# P03_Processor_2_or_3_USB_and_Serial.net
KiCad netlist of a schematic drawn in Altium Designer
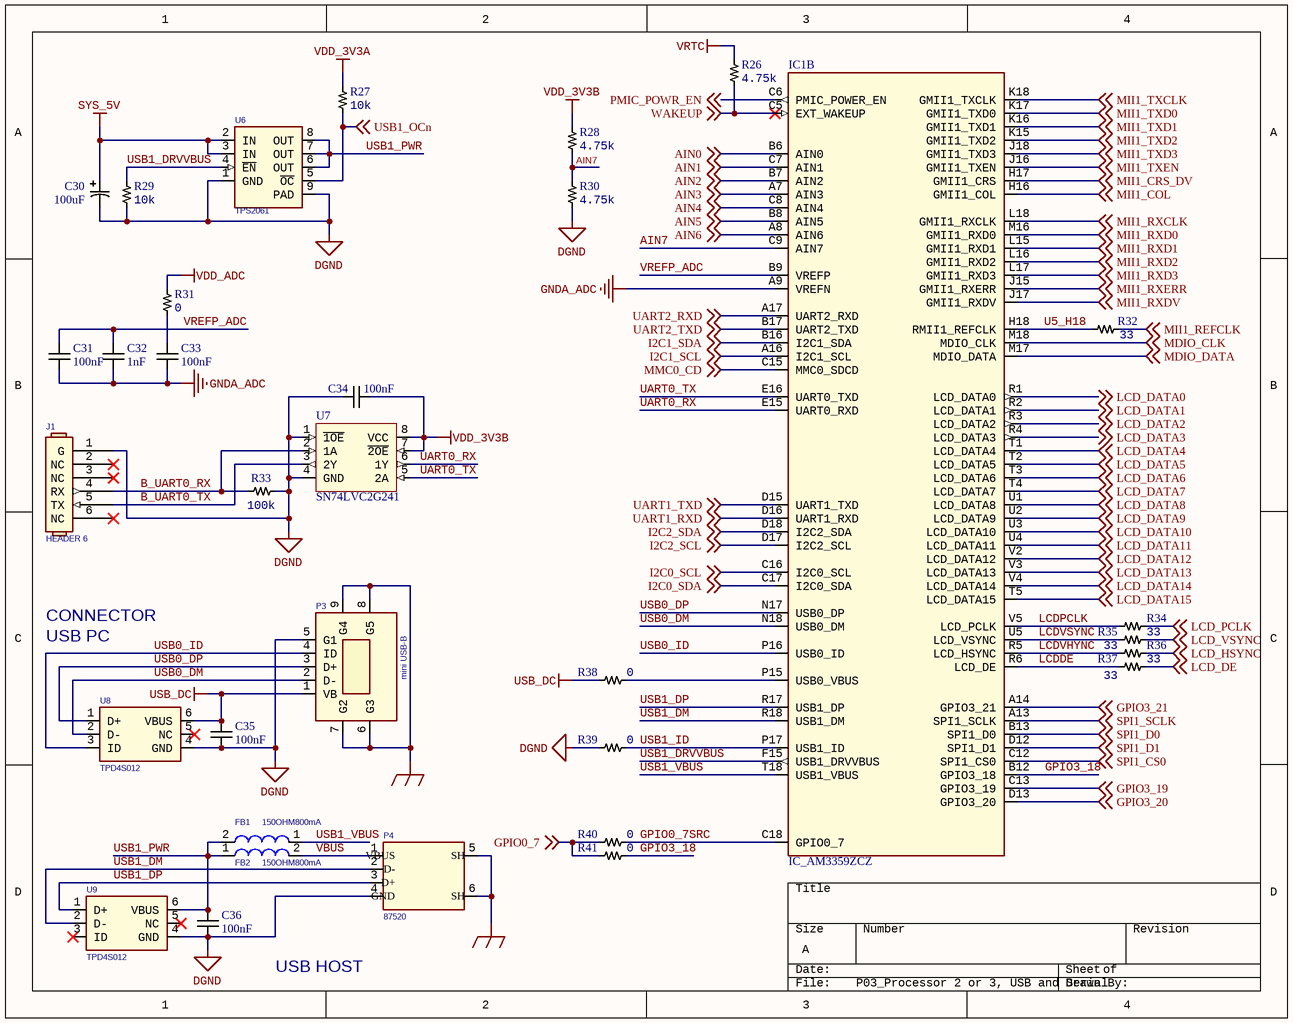
[diagram p0: P03_Processor 2 or 3, USB and Serial.SchDoc]

(export (version "E")
  (design (tool "Eeschema 10.0.6"))
  (components
    (comp (ref "C30")
      (value "EEE-0JA101SP")
      (footprint "CAP6.6x6.6")
      (description "POL CAP 100uF SMD")
      (fields
        (field (name "MANUFACTURER") "Panasonic")
        (field (name "TOLERANCE") "20%")
        (field (name "CAPACITANCE") "100uF")
      )
      (libsource (lib "Orient2") (part "CAP_POL_100uF"))
    )
    (comp (ref "C31")
      (value "C0402C104K4RACTU")
      (footprint "CAP0402")
      (description "MLCC 100nF 0402 SMD")
      (fields
        (field (name "MANUFACTURER") "KEMET")
        (field (name "CAPACITANCE") "100nF")
        (field (name "TOLERANCE") "10%")
      )
      (libsource (lib "Orient2") (part "CAP_100nF"))
    )
    (comp (ref "C32")
      (value "CC0402KRX7R9BB102")
      (footprint "CAP0402")
      (description "MLCC 1nF 0402 SMD")
      (fields
        (field (name "MANUFACTURER") "Yageo")
        (field (name "CAPACITANCE") "1nF")
        (field (name "TOLERANCE") "10%")
      )
      (libsource (lib "Orient2") (part "CAP_1nF"))
    )
    (comp (ref "C33")
      (value "C0402C104K4RACTU")
      (footprint "CAP0402")
      (description "MLCC 100nF 0402 SMD")
      (fields
        (field (name "MANUFACTURER") "KEMET")
        (field (name "CAPACITANCE") "100nF")
        (field (name "TOLERANCE") "10%")
      )
      (libsource (lib "Orient2") (part "CAP_100nF"))
    )
    (comp (ref "C34")
      (value "C0402C104K4RACTU")
      (footprint "CAP0402")
      (description "MLCC 100nF 0402 SMD")
      (fields
        (field (name "MANUFACTURER") "KEMET")
        (field (name "CAPACITANCE") "100nF")
        (field (name "TOLERANCE") "10%")
      )
      (libsource (lib "Orient2") (part "CAP_100nF"))
    )
    (comp (ref "C35")
      (value "C0402C104K4RACTU")
      (footprint "CAP0402")
      (description "MLCC 100nF 0402 SMD")
      (fields
        (field (name "MANUFACTURER") "KEMET")
        (field (name "CAPACITANCE") "100nF")
        (field (name "TOLERANCE") "10%")
      )
      (libsource (lib "Orient2") (part "CAP_100nF"))
    )
    (comp (ref "C36")
      (value "C0402C104K4RACTU")
      (footprint "CAP0402")
      (description "MLCC 100nF 0402 SMD")
      (fields
        (field (name "MANUFACTURER") "KEMET")
        (field (name "CAPACITANCE") "100nF")
        (field (name "TOLERANCE") "10%")
      )
      (libsource (lib "Orient2") (part "CAP_100nF"))
    )
    (comp (ref "FB1")
      (value "150OHM800mA")
      (footprint "FB0805")
      (description "FERRITE 800MA 150 OHM 0805 SMD")
      (fields
        (field (name "MANUFACTURER") "Laird-Signal Integrity Products")
        (field (name "MANUFACTURER PART NUMBER") "LI0805H151R-10")
      )
      (libsource (lib "") (part "FERR_1"))
    )
    (comp (ref "FB2")
      (value "150OHM800mA")
      (footprint "FB0805")
      (description "FERRITE 800MA 150 OHM 0805 SMD")
      (fields (field (name "MFR") "Steward") (field (name "TIINTPARTNUMBER") "1L0010"))
      (libsource (lib "Orient2") (part "FERR"))
    )
    (comp (ref "IC1")
      (value "IC_AM3359ZCZ")
      (footprint "BGA-324")
      (description "SubArctic Cortex A8 Processor 18x18")
      (fields
        (field (name "MANUFACTURER") "Texas Instruments")
        (field (name "MANUFACTURER PART NUMBER") "XAM3359ZCZ")
      )
      (libsource (lib "Orient2") (part "IC_AM335X_ZCE_1"))
    )
    (comp (ref "J1")
      (value "HEADER 6")
      (footprint "SIP6")
      (description "CONN HEADER 6POS, VERTICAL,  .100 STR TIN")
      (fields
        (field (name "MANUFACTURER") "Samtec Inc")
        (field (name "MANUFACTURER PART NUMBER") "FTR-110-03-G-D-06")
      )
      (libsource (lib "Orient2") (part "HDR_6x1"))
    )
    (comp (ref "P3")
      (value "mini USB-B")
      (footprint "USB5MINI_4SHIELDED_SMD-5")
      (description "CONN RCPT USB MINI B R/A SMD")
      (fields (field (name "MANUFACTURER") "KYCON") (field (name "MANUFACTURER PART NUMBER") "0565790576"))
      (libsource (lib "Orient2") (part "MINI-USB-AB-SOCKET"))
    )
    (comp (ref "P4")
      (value "87520")
      (footprint "USB_A")
      (description "CONN RCPT USB TYPE A R/A PCB")
      (fields (field (name "MANUFACTURER") "FCI") (field (name "MANUFACTURER PART NUMBER") "87520-0010BLF"))
      (libsource (lib "Orient2") (part "CONN_USBA"))
    )
    (comp (ref "R26")
      (value "RC0402FR-074K75L")
      (footprint "RES0402")
      (description "Resistor 4.75kOhm 0402 SMD")
      (fields
        (field (name "MANUFACTURER") "Yageo")
        (field (name "TOLERANCE") "1%")
        (field (name "RESISTANCE") "4.75k")
      )
      (libsource (lib "Orient2") (part "RES_4.75k"))
    )
    (comp (ref "R27")
      (value "RC0402FR-0710KL")
      (footprint "RES0402")
      (description "Resistor 10kOhm 0402 SMD")
      (fields
        (field (name "MANUFACTURER") "Yageo")
        (field (name "TOLERANCE") "1%")
        (field (name "RESISTANCE") "10k")
      )
      (libsource (lib "Orient2") (part "RES_10k"))
    )
    (comp (ref "R28")
      (value "RC0402FR-074K75L")
      (footprint "RES0402")
      (description "Resistor 4.75kOhm 0402 SMD")
      (fields
        (field (name "MANUFACTURER") "Yageo")
        (field (name "TOLERANCE") "1%")
        (field (name "RESISTANCE") "4.75k")
      )
      (libsource (lib "Orient2") (part "RES_4.75k"))
    )
    (comp (ref "R29")
      (value "RC0402FR-0710KL")
      (footprint "RES0402")
      (description "Resistor 10kOhm 0402 SMD")
      (fields
        (field (name "MANUFACTURER") "Yageo")
        (field (name "TOLERANCE") "1%")
        (field (name "RESISTANCE") "10k")
      )
      (libsource (lib "Orient2") (part "RES_10k"))
    )
    (comp (ref "R30")
      (value "RC0402FR-074K75L")
      (footprint "RES0402")
      (description "Resistor 4.75kOhm 0402 SMD")
      (fields
        (field (name "MANUFACTURER") "Yageo")
        (field (name "TOLERANCE") "1%")
        (field (name "RESISTANCE") "4.75k")
      )
      (libsource (lib "Orient2") (part "RES_4.75k"))
    )
    (comp (ref "R31")
      (value "RC0402JR-070RL")
      (footprint "RES0402")
      (description "Resistor 0Ohm 0402 SMD")
      (fields
        (field (name "MANUFACTURER") "Yageo")
        (field (name "TOLERANCE") "5%")
        (field (name "RESISTANCE") "0")
      )
      (libsource (lib "Orient2") (part "RES_0"))
    )
    (comp (ref "R32")
      (value "RC0402FR-0733RL")
      (footprint "RES0402")
      (description "Resistor 33Ohm 0402 SMD")
      (fields
        (field (name "MANUFACTURER") "Yageo")
        (field (name "TOLERANCE") "1%")
        (field (name "RESISTANCE") "33")
      )
      (libsource (lib "Orient2") (part "RES_33"))
    )
    (comp (ref "R33")
      (value "RC0402FR-07100KL")
      (footprint "RES0402")
      (description "Resistor 100kOhm 0402 SMD")
      (fields
        (field (name "MANUFACTURER") "Yageo")
        (field (name "TOLERANCE") "1%")
        (field (name "RESISTANCE") "100k")
      )
      (libsource (lib "Orient2") (part "RES_100k"))
    )
    (comp (ref "R34")
      (value "RC0402FR-0733RL")
      (footprint "RES0402")
      (description "Resistor 33Ohm 0402 SMD")
      (fields
        (field (name "MANUFACTURER") "Yageo")
        (field (name "TOLERANCE") "1%")
        (field (name "RESISTANCE") "33")
      )
      (libsource (lib "Orient2") (part "RES_33"))
    )
    (comp (ref "R35")
      (value "RC0402FR-0733RL")
      (footprint "RES0402")
      (description "Resistor 33Ohm 0402 SMD")
      (fields
        (field (name "MANUFACTURER") "Yageo")
        (field (name "TOLERANCE") "1%")
        (field (name "RESISTANCE") "33")
      )
      (libsource (lib "Orient2") (part "RES_33"))
    )
    (comp (ref "R36")
      (value "RC0402FR-0733RL")
      (footprint "RES0402")
      (description "Resistor 33Ohm 0402 SMD")
      (fields
        (field (name "MANUFACTURER") "Yageo")
        (field (name "TOLERANCE") "1%")
        (field (name "RESISTANCE") "33")
      )
      (libsource (lib "Orient2") (part "RES_33"))
    )
    (comp (ref "R37")
      (value "RC0402FR-0733RL")
      (footprint "RES0402")
      (description "Resistor 33Ohm 0402 SMD")
      (fields
        (field (name "MANUFACTURER") "Yageo")
        (field (name "TOLERANCE") "1%")
        (field (name "RESISTANCE") "33")
      )
      (libsource (lib "Orient2") (part "RES_33"))
    )
    (comp (ref "R38")
      (value "RC0402JR-070RL")
      (footprint "RES0402")
      (description "Resistor 0Ohm 0402 SMD")
      (fields
        (field (name "MANUFACTURER") "Yageo")
        (field (name "TOLERANCE") "5%")
        (field (name "RESISTANCE") "0")
      )
      (libsource (lib "Orient2") (part "RES_0"))
    )
    (comp (ref "R39")
      (value "RC0402JR-070RL")
      (footprint "RES0402")
      (description "Resistor 0Ohm 0402 SMD")
      (fields
        (field (name "MANUFACTURER") "Yageo")
        (field (name "TOLERANCE") "5%")
        (field (name "RESISTANCE") "0")
      )
      (libsource (lib "Orient2") (part "RES_0"))
    )
    (comp (ref "R40")
      (value "RC0402JR-070RL")
      (footprint "RES0402")
      (description "Resistor 0Ohm 0402 SMD")
      (fields
        (field (name "MANUFACTURER") "Yageo")
        (field (name "TOLERANCE") "5%")
        (field (name "RESISTANCE") "0")
      )
      (libsource (lib "Orient2") (part "RES_0"))
    )
    (comp (ref "R41")
      (value "RC0402JR-070RL")
      (footprint "RES0402")
      (description "Resistor 0Ohm 0402 SMD")
      (fields
        (field (name "MANUFACTURER") "Yageo")
        (field (name "TOLERANCE") "5%")
        (field (name "RESISTANCE") "0")
      )
      (libsource (lib "Orient2") (part "RES_0"))
    )
    (comp (ref "U6")
      (value "TPS2061")
      (footprint "HVSSOP-8")
      (description "IC 1.5A PWR DIST SWITCH 8-SOIC")
      (fields
        (field (name "MANUFACTURER") "Texas Instruments")
        (field (name "MANUFACTURER PART NUMBER") "TPS2051BDGNR")
      )
      (libsource (lib "Orient2") (part "TPS2061"))
    )
    (comp (ref "U7")
      (value "SN74LVC2G241")
      (footprint "VSSOP-8")
      (description "IC BUFF/DVR TRI-ST DL 8VSSOP")
      (fields
        (field (name "MANUFACTURER") "Texas Instruments")
        (field (name "MANUFACTURER PART NUMBER") "SN74LVC2G241DCUR")
      )
      (libsource (lib "Orient2") (part "SN74LVC2G241"))
    )
    (comp (ref "U8")
      (value "TPD4S012")
      (footprint "U_6_DRY")
      (description "ESD 4channel USB Interface")
      (fields (field (name "MFR") "TI") (field (name "TIINTPARTNUMBER") "1A0233"))
      (libsource (lib "Orient2") (part "PROT_TPD4S012"))
    )
    (comp (ref "U9")
      (value "TPD4S012")
      (footprint "U_6_DRY")
      (description "ESD 4channel USB Interface")
      (fields (field (name "MFR") "TI") (field (name "TIINTPARTNUMBER") "1A0233"))
      (libsource (lib "Orient2") (part "PROT_TPD4S012"))
    )
  )
  (nets
    (net (code "1") (name "/AIN7") (class "Default")
      (node (ref "IC1") (pin "C9") (pinfunction "AIN7_C9") (pintype "passive"))
      (node (ref "R28") (pin "1") (pintype "passive"))
      (node (ref "R30") (pin "2") (pintype "passive"))
    )
    (net (code "2") (name "/B_UART0_RX") (class "Default")
      (node (ref "J1") (pin "4") (pinfunction "RX_4") (pintype "output"))
      (node (ref "R33") (pin "2") (pintype "passive"))
      (node (ref "U7") (pin "2") (pinfunction "1A_2") (pintype "input"))
    )
    (net (code "3") (name "/B_UART0_TX") (class "Default")
      (node (ref "J1") (pin "5") (pinfunction "TX_5") (pintype "input"))
      (node (ref "U7") (pin "3") (pinfunction "2Y_3") (pintype "output"))
    )
    (net (code "4") (name "/GPIO0_7SRC") (class "Default")
      (node (ref "IC1") (pin "C18") (pinfunction "GPIO0_7_C18") (pintype "bidirectional"))
      (node (ref "R40") (pin "1") (pintype "passive"))
    )
    (net (code "5") (name "/GPIO3_18") (class "Default")
      (node (ref "IC1") (pin "B12") (pinfunction "GPIO3_18_B12") (pintype "bidirectional"))
      (node (ref "R41") (pin "2") (pintype "passive"))
    )
    (net (code "6") (name "/LCDDE") (class "Default")
      (node (ref "IC1") (pin "R6") (pinfunction "LCD_DE_R6") (pintype "bidirectional"))
      (node (ref "R37") (pin "1") (pintype "passive"))
    )
    (net (code "7") (name "/LCDPCLK") (class "Default")
      (node (ref "IC1") (pin "V5") (pinfunction "LCD_PCLK_V5") (pintype "bidirectional"))
      (node (ref "R34") (pin "1") (pintype "passive"))
    )
    (net (code "8") (name "/LCDVHYNC") (class "Default")
      (node (ref "IC1") (pin "R5") (pinfunction "LCD_HSYNC_R5") (pintype "bidirectional"))
      (node (ref "R36") (pin "1") (pintype "passive"))
    )
    (net (code "9") (name "/LCDVSYNC") (class "Default")
      (node (ref "IC1") (pin "U5") (pinfunction "LCD_VSYNC_U5") (pintype "bidirectional"))
      (node (ref "R35") (pin "1") (pintype "passive"))
    )
    (net (code "10") (name "/U5_H18") (class "Default")
      (node (ref "IC1") (pin "H18") (pinfunction "RMII1_REFCLK_H18") (pintype "bidirectional"))
      (node (ref "R32") (pin "1") (pintype "passive"))
    )
    (net (code "11") (name "/UART0_RX") (class "Default")
      (node (ref "IC1") (pin "E15") (pinfunction "UART0_RXD_E15") (pintype "bidirectional"))
      (node (ref "U7") (pin "6") (pinfunction "1Y_6") (pintype "output"))
    )
    (net (code "12") (name "/UART0_TX") (class "Default")
      (node (ref "IC1") (pin "E16") (pinfunction "UART0_TXD_E16") (pintype "bidirectional"))
      (node (ref "U7") (pin "5") (pinfunction "2A_5") (pintype "input"))
    )
    (net (code "13") (name "/USB0_DM") (class "Default")
      (node (ref "IC1") (pin "N18") (pinfunction "USB0_DM_N18") (pintype "bidirectional"))
      (node (ref "P3") (pin "2") (pinfunction "D-_2") (pintype "passive"))
      (node (ref "U8") (pin "2") (pinfunction "D-_2") (pintype "passive"))
    )
    (net (code "14") (name "/USB0_DP") (class "Default")
      (node (ref "IC1") (pin "N17") (pinfunction "USB0_DP_N17") (pintype "bidirectional"))
      (node (ref "P3") (pin "3") (pinfunction "D+_3") (pintype "passive"))
      (node (ref "U8") (pin "1") (pinfunction "D+_1") (pintype "passive"))
    )
    (net (code "15") (name "/USB0_ID") (class "Default")
      (node (ref "IC1") (pin "P16") (pinfunction "USB0_ID_P16") (pintype "passive"))
      (node (ref "P3") (pin "4") (pinfunction "ID_4") (pintype "passive"))
      (node (ref "U8") (pin "3") (pinfunction "ID_3") (pintype "passive"))
    )
    (net (code "16") (name "/USB1_DM") (class "Default")
      (node (ref "IC1") (pin "R18") (pinfunction "USB1_DM_R18") (pintype "bidirectional"))
      (node (ref "P4") (pin "2") (pinfunction "P2_2") (pintype "passive"))
      (node (ref "U9") (pin "2") (pinfunction "D-_2") (pintype "passive"))
    )
    (net (code "17") (name "/USB1_DP") (class "Default")
      (node (ref "IC1") (pin "R17") (pinfunction "USB1_DP_R17") (pintype "bidirectional"))
      (node (ref "P4") (pin "3") (pinfunction "P3_3") (pintype "passive"))
      (node (ref "U9") (pin "1") (pinfunction "D+_1") (pintype "passive"))
    )
    (net (code "18") (name "/USB1_DRVVBUS") (class "Default")
      (node (ref "IC1") (pin "F15") (pinfunction "USB1_DRVVBUS_F15") (pintype "output"))
      (node (ref "R29") (pin "1") (pintype "passive"))
      (node (ref "U6") (pin "4") (pinfunction "~{EN}_4") (pintype "input"))
    )
    (net (code "19") (name "/USB1_ID") (class "Default")
      (node (ref "IC1") (pin "P17") (pinfunction "USB1_ID_P17") (pintype "passive"))
      (node (ref "R39") (pin "2") (pintype "passive"))
    )
    (net (code "20") (name "/USB1_PWR") (class "Default")
      (node (ref "C36") (pin "1") (pintype "passive"))
      (node (ref "FB1") (pin "2") (pinfunction "2_2") (pintype "passive"))
      (node (ref "FB2") (pin "1") (pinfunction "1_1") (pintype "passive"))
      (node (ref "U6") (pin "6") (pinfunction "OUT_6") (pintype "power_in"))
      (node (ref "U6") (pin "7") (pinfunction "OUT_7") (pintype "power_in"))
      (node (ref "U6") (pin "8") (pinfunction "OUT_8") (pintype "power_in"))
      (node (ref "U9") (pin "6") (pinfunction "VBUS_6") (pintype "power_in"))
    )
    (net (code "21") (name "/USB1_VBUS") (class "Default")
      (node (ref "FB1") (pin "1") (pinfunction "1_1") (pintype "passive"))
      (node (ref "IC1") (pin "T18") (pinfunction "USB1_VBUS_T18") (pintype "passive"))
    )
    (net (code "22") (name "/VBUS") (class "Default")
      (node (ref "FB2") (pin "2") (pinfunction "2_2") (pintype "passive"))
      (node (ref "P4") (pin "1") (pinfunction "P1_1") (pintype "passive"))
    )
    (net (code "23") (name "/VREFP_ADC") (class "Default")
      (node (ref "C31") (pin "1") (pintype "passive"))
      (node (ref "C32") (pin "1") (pintype "passive"))
      (node (ref "IC1") (pin "B9") (pinfunction "VREFP_B9") (pintype "passive"))
    )
    (net (code "24") (name "AIN0") (class "Default")
      (node (ref "IC1") (pin "B6") (pinfunction "AIN0_B6") (pintype "passive"))
    )
    (net (code "25") (name "AIN1") (class "Default")
      (node (ref "IC1") (pin "C7") (pinfunction "AIN1_C7") (pintype "passive"))
    )
    (net (code "26") (name "AIN2") (class "Default")
      (node (ref "IC1") (pin "B7") (pinfunction "AIN2_B7") (pintype "passive"))
    )
    (net (code "27") (name "AIN3") (class "Default")
      (node (ref "IC1") (pin "A7") (pinfunction "AIN3_A7") (pintype "passive"))
    )
    (net (code "28") (name "AIN4") (class "Default")
      (node (ref "IC1") (pin "C8") (pinfunction "AIN4_C8") (pintype "passive"))
    )
    (net (code "29") (name "AIN5") (class "Default")
      (node (ref "IC1") (pin "B8") (pinfunction "AIN5_B8") (pintype "passive"))
    )
    (net (code "30") (name "AIN6") (class "Default")
      (node (ref "IC1") (pin "A8") (pinfunction "AIN6_A8") (pintype "passive"))
    )
    (net (code "31") (name "DGND") (class "Default")
      (node (ref "C30") (pin "2") (pinfunction "C_2") (pintype "passive"))
      (node (ref "C34") (pin "1") (pintype "passive"))
      (node (ref "C35") (pin "2") (pintype "passive"))
      (node (ref "C36") (pin "2") (pintype "passive"))
      (node (ref "J1") (pin "1") (pinfunction "G_1") (pintype "power_in"))
      (node (ref "P3") (pin "5") (pinfunction "G1_5") (pintype "passive"))
      (node (ref "P4") (pin "4") (pinfunction "P4_4") (pintype "passive"))
      (node (ref "R29") (pin "2") (pintype "passive"))
      (node (ref "R30") (pin "1") (pintype "passive"))
      (node (ref "R33") (pin "1") (pintype "passive"))
      (node (ref "R39") (pin "1") (pintype "passive"))
      (node (ref "U6") (pin "1") (pinfunction "GND_1") (pintype "power_in"))
      (node (ref "U6") (pin "9") (pinfunction "PAD_9") (pintype "passive"))
      (node (ref "U7") (pin "1") (pinfunction "~{1OE}_1") (pintype "input"))
      (node (ref "U7") (pin "4") (pinfunction "GND_4") (pintype "power_in"))
      (node (ref "U8") (pin "4") (pinfunction "GND_4") (pintype "power_in"))
      (node (ref "U9") (pin "4") (pinfunction "GND_4") (pintype "power_in"))
    )
    (net (code "32") (name "GNDA_ADC") (class "Default")
      (node (ref "C31") (pin "2") (pintype "passive"))
      (node (ref "C32") (pin "2") (pintype "passive"))
      (node (ref "C33") (pin "2") (pintype "passive"))
      (node (ref "IC1") (pin "A9") (pinfunction "VREFN_A9") (pintype "passive"))
    )
    (net (code "33") (name "GND_EARTH") (class "Default")
      (node (ref "P3") (pin "6") (pinfunction "G3_6") (pintype "passive"))
      (node (ref "P3") (pin "7") (pinfunction "G2_7") (pintype "passive"))
      (node (ref "P3") (pin "8") (pinfunction "G5_8") (pintype "passive"))
      (node (ref "P3") (pin "9") (pinfunction "G4_9") (pintype "passive"))
      (node (ref "P4") (pin "5") (pinfunction "SHELD1_5") (pintype "passive"))
      (node (ref "P4") (pin "6") (pinfunction "PAD4_6") (pintype "passive"))
    )
    (net (code "34") (name "GPIO0_7") (class "Default")
      (node (ref "R40") (pin "2") (pintype "passive"))
      (node (ref "R41") (pin "1") (pintype "passive"))
    )
    (net (code "35") (name "GPIO3_19") (class "Default")
      (node (ref "IC1") (pin "C13") (pinfunction "GPIO3_19_C13") (pintype "bidirectional"))
    )
    (net (code "36") (name "GPIO3_20") (class "Default")
      (node (ref "IC1") (pin "D13") (pinfunction "GPIO3_20_D13") (pintype "bidirectional"))
    )
    (net (code "37") (name "GPIO3_21") (class "Default")
      (node (ref "IC1") (pin "A14") (pinfunction "GPIO3_21_A14") (pintype "bidirectional"))
    )
    (net (code "38") (name "I2C0_SCL") (class "Default")
      (node (ref "IC1") (pin "C16") (pinfunction "I2C0_SCL_C16") (pintype "bidirectional"))
    )
    (net (code "39") (name "I2C0_SDA") (class "Default")
      (node (ref "IC1") (pin "C17") (pinfunction "I2C0_SDA_C17") (pintype "bidirectional"))
    )
    (net (code "40") (name "I2C1_SCL") (class "Default")
      (node (ref "IC1") (pin "A16") (pinfunction "I2C1_SCL_A16") (pintype "bidirectional"))
    )
    (net (code "41") (name "I2C1_SDA") (class "Default")
      (node (ref "IC1") (pin "B16") (pinfunction "I2C1_SDA_B16") (pintype "bidirectional"))
    )
    (net (code "42") (name "I2C2_SCL") (class "Default")
      (node (ref "IC1") (pin "D17") (pinfunction "I2C2_SCL_D17") (pintype "bidirectional"))
    )
    (net (code "43") (name "I2C2_SDA") (class "Default")
      (node (ref "IC1") (pin "D18") (pinfunction "I2C2_SDA_D18") (pintype "bidirectional"))
    )
    (net (code "44") (name "LCD_DATA0") (class "Default")
      (node (ref "IC1") (pin "R1") (pinfunction "LCD_DATA0_R1") (pintype "output"))
    )
    (net (code "45") (name "LCD_DATA1") (class "Default")
      (node (ref "IC1") (pin "R2") (pinfunction "LCD_DATA1_R2") (pintype "output"))
    )
    (net (code "46") (name "LCD_DATA2") (class "Default")
      (node (ref "IC1") (pin "R3") (pinfunction "LCD_DATA2_R3") (pintype "output"))
    )
    (net (code "47") (name "LCD_DATA3") (class "Default")
      (node (ref "IC1") (pin "R4") (pinfunction "LCD_DATA3_R4") (pintype "output"))
    )
    (net (code "48") (name "LCD_DATA4") (class "Default")
      (node (ref "IC1") (pin "T1") (pinfunction "LCD_DATA4_T1") (pintype "bidirectional"))
    )
    (net (code "49") (name "LCD_DATA5") (class "Default")
      (node (ref "IC1") (pin "T2") (pinfunction "LCD_DATA5_T2") (pintype "bidirectional"))
    )
    (net (code "50") (name "LCD_DATA6") (class "Default")
      (node (ref "IC1") (pin "T3") (pinfunction "LCD_DATA6_T3") (pintype "bidirectional"))
    )
    (net (code "51") (name "LCD_DATA7") (class "Default")
      (node (ref "IC1") (pin "T4") (pinfunction "LCD_DATA7_T4") (pintype "bidirectional"))
    )
    (net (code "52") (name "LCD_DATA8") (class "Default")
      (node (ref "IC1") (pin "U1") (pinfunction "LCD_DATA8_U1") (pintype "bidirectional"))
    )
    (net (code "53") (name "LCD_DATA9") (class "Default")
      (node (ref "IC1") (pin "U2") (pinfunction "LCD_DATA9_U2") (pintype "bidirectional"))
    )
    (net (code "54") (name "LCD_DATA10") (class "Default")
      (node (ref "IC1") (pin "U3") (pinfunction "LCD_DATA10_U3") (pintype "bidirectional"))
    )
    (net (code "55") (name "LCD_DATA11") (class "Default")
      (node (ref "IC1") (pin "U4") (pinfunction "LCD_DATA11_U4") (pintype "bidirectional"))
    )
    (net (code "56") (name "LCD_DATA12") (class "Default")
      (node (ref "IC1") (pin "V2") (pinfunction "LCD_DATA12_V2") (pintype "bidirectional"))
    )
    (net (code "57") (name "LCD_DATA13") (class "Default")
      (node (ref "IC1") (pin "V3") (pinfunction "LCD_DATA13_V3") (pintype "bidirectional"))
    )
    (net (code "58") (name "LCD_DATA14") (class "Default")
      (node (ref "IC1") (pin "V4") (pinfunction "LCD_DATA14_V4") (pintype "bidirectional"))
    )
    (net (code "59") (name "LCD_DATA15") (class "Default")
      (node (ref "IC1") (pin "T5") (pinfunction "LCD_DATA15_T5") (pintype "bidirectional"))
    )
    (net (code "60") (name "LCD_DE") (class "Default") (node (ref "R37") (pin "2") (pintype "passive")))
    (net (code "61") (name "LCD_HSYNC") (class "Default") (node (ref "R36") (pin "2") (pintype "passive")))
    (net (code "62") (name "LCD_PCLK") (class "Default") (node (ref "R34") (pin "2") (pintype "passive")))
    (net (code "63") (name "LCD_VSYNC") (class "Default") (node (ref "R35") (pin "2") (pintype "passive")))
    (net (code "64") (name "MDIO_CLK") (class "Default")
      (node (ref "IC1") (pin "M18") (pinfunction "MDIO_CLK_M18") (pintype "bidirectional"))
    )
    (net (code "65") (name "MDIO_DATA") (class "Default")
      (node (ref "IC1") (pin "M17") (pinfunction "MDIO_DATA_M17") (pintype "bidirectional"))
    )
    (net (code "66") (name "MII1_COL") (class "Default")
      (node (ref "IC1") (pin "H16") (pinfunction "GMII1_COL_H16") (pintype "bidirectional"))
    )
    (net (code "67") (name "MII1_CRS_DV") (class "Default")
      (node (ref "IC1") (pin "H17") (pinfunction "GMII1_CRS_H17") (pintype "bidirectional"))
    )
    (net (code "68") (name "MII1_REFCLK") (class "Default") (node (ref "R32") (pin "2") (pintype "passive")))
    (net (code "69") (name "MII1_RXCLK") (class "Default")
      (node (ref "IC1") (pin "L18") (pinfunction "GMII1_RXCLK_L18") (pintype "bidirectional"))
    )
    (net (code "70") (name "MII1_RXD0") (class "Default")
      (node (ref "IC1") (pin "M16") (pinfunction "GMII1_RXD0_M16") (pintype "passive"))
    )
    (net (code "71") (name "MII1_RXD1") (class "Default")
      (node (ref "IC1") (pin "L15") (pinfunction "GMII1_RXD1_L15") (pintype "bidirectional"))
    )
    (net (code "72") (name "MII1_RXD2") (class "Default")
      (node (ref "IC1") (pin "L16") (pinfunction "GMII1_RXD2_L16") (pintype "bidirectional"))
    )
    (net (code "73") (name "MII1_RXD3") (class "Default")
      (node (ref "IC1") (pin "L17") (pinfunction "GMII1_RXD3_L17") (pintype "bidirectional"))
    )
    (net (code "74") (name "MII1_RXDV") (class "Default")
      (node (ref "IC1") (pin "J17") (pinfunction "GMII1_RXDV_J17") (pintype "bidirectional"))
    )
    (net (code "75") (name "MII1_RXERR") (class "Default")
      (node (ref "IC1") (pin "J15") (pinfunction "GMII1_RXERR_J15") (pintype "bidirectional"))
    )
    (net (code "76") (name "MII1_TXCLK") (class "Default")
      (node (ref "IC1") (pin "K18") (pinfunction "GMII1_TXCLK_K18") (pintype "bidirectional"))
    )
    (net (code "77") (name "MII1_TXD0") (class "Default")
      (node (ref "IC1") (pin "K17") (pinfunction "GMII1_TXD0_K17") (pintype "bidirectional"))
    )
    (net (code "78") (name "MII1_TXD1") (class "Default")
      (node (ref "IC1") (pin "K16") (pinfunction "GMII1_TXD1_K16") (pintype "bidirectional"))
    )
    (net (code "79") (name "MII1_TXD2") (class "Default")
      (node (ref "IC1") (pin "K15") (pinfunction "GMII1_TXD2_K15") (pintype "bidirectional"))
    )
    (net (code "80") (name "MII1_TXD3") (class "Default")
      (node (ref "IC1") (pin "J18") (pinfunction "GMII1_TXD3_J18") (pintype "bidirectional"))
    )
    (net (code "81") (name "MII1_TXEN") (class "Default")
      (node (ref "IC1") (pin "J16") (pinfunction "GMII1_TXEN_J16") (pintype "bidirectional"))
    )
    (net (code "82") (name "MMC0_CD") (class "Default")
      (node (ref "IC1") (pin "C15") (pinfunction "MMC0_SDCD_C15") (pintype "bidirectional"))
    )
    (net (code "83") (name "Net-(C33-Pad1)") (class "Default")
      (node (ref "C33") (pin "1") (pintype "passive"))
      (node (ref "R31") (pin "1") (pintype "passive"))
    )
    (net (code "84") (name "Net-(IC1B-USB0_VBUS)") (class "Default")
      (node (ref "IC1") (pin "P15") (pinfunction "USB0_VBUS_P15") (pintype "passive"))
      (node (ref "R38") (pin "2") (pintype "passive"))
    )
    (net (code "85") (name "PMIC_POWR_EN") (class "Default")
      (node (ref "IC1") (pin "C6") (pinfunction "PMIC_POWER_EN_C6") (pintype "output"))
    )
    (net (code "86") (name "SPI1_CS0") (class "Default")
      (node (ref "IC1") (pin "C12") (pinfunction "SPI1_CS0_C12") (pintype "bidirectional"))
    )
    (net (code "87") (name "SPI1_D0") (class "Default")
      (node (ref "IC1") (pin "B13") (pinfunction "SPI1_D0_B13") (pintype "bidirectional"))
    )
    (net (code "88") (name "SPI1_D1") (class "Default")
      (node (ref "IC1") (pin "D12") (pinfunction "SPI1_D1_D12") (pintype "bidirectional"))
    )
    (net (code "89") (name "SPI1_SCLK") (class "Default")
      (node (ref "IC1") (pin "A13") (pinfunction "SPI1_SCLK_A13") (pintype "bidirectional"))
    )
    (net (code "90") (name "SYS_5V") (class "Default")
      (node (ref "C30") (pin "1") (pinfunction "A_1") (pintype "passive"))
      (node (ref "U6") (pin "2") (pinfunction "IN_2") (pintype "power_in"))
      (node (ref "U6") (pin "3") (pinfunction "IN_3") (pintype "power_in"))
    )
    (net (code "91") (name "UART1_RXD") (class "Default")
      (node (ref "IC1") (pin "D16") (pinfunction "UART1_RXD_D16") (pintype "bidirectional"))
    )
    (net (code "92") (name "UART1_TXD") (class "Default")
      (node (ref "IC1") (pin "D15") (pinfunction "UART1_TXD_D15") (pintype "bidirectional"))
    )
    (net (code "93") (name "UART2_RXD") (class "Default")
      (node (ref "IC1") (pin "A17") (pinfunction "UART2_RXD_A17") (pintype "bidirectional"))
    )
    (net (code "94") (name "UART2_TXD") (class "Default")
      (node (ref "IC1") (pin "B17") (pinfunction "UART2_TXD_B17") (pintype "bidirectional"))
    )
    (net (code "95") (name "USB1_OCn") (class "Default")
      (node (ref "R27") (pin "2") (pintype "passive"))
      (node (ref "U6") (pin "5") (pinfunction "~{OC}_5") (pintype "passive"))
    )
    (net (code "96") (name "USB_DC") (class "Default")
      (node (ref "C35") (pin "1") (pintype "passive"))
      (node (ref "P3") (pin "1") (pinfunction "VB_1") (pintype "passive"))
      (node (ref "R38") (pin "1") (pintype "passive"))
      (node (ref "U8") (pin "6") (pinfunction "VBUS_6") (pintype "power_in"))
    )
    (net (code "97") (name "VDD_3V3A") (class "Default") (node (ref "R27") (pin "1") (pintype "passive")))
    (net (code "98") (name "VDD_3V3B") (class "Default")
      (node (ref "C34") (pin "2") (pintype "passive"))
      (node (ref "R28") (pin "2") (pintype "passive"))
      (node (ref "U7") (pin "7") (pinfunction "~{2OE}_7") (pintype "input"))
      (node (ref "U7") (pin "8") (pinfunction "VCC_8") (pintype "power_in"))
    )
    (net (code "99") (name "VDD_ADC") (class "Default") (node (ref "R31") (pin "2") (pintype "passive")))
    (net (code "100") (name "VRTC") (class "Default") (node (ref "R26") (pin "2") (pintype "passive")))
    (net (code "101") (name "WAKEUP") (class "Default")
      (node (ref "IC1") (pin "C5") (pinfunction "EXT_WAKEUP_C5") (pintype "input"))
      (node (ref "R26") (pin "1") (pintype "passive"))
    )
    (net (code "102") (name "unconnected-(J1-NC-Pad2)") (class "Default")
      (node (ref "J1") (pin "2") (pinfunction "NC_2") (pintype "passive+no_connect"))
    )
    (net (code "103") (name "unconnected-(J1-NC-Pad3)") (class "Default")
      (node (ref "J1") (pin "3") (pinfunction "NC_3") (pintype "passive+no_connect"))
    )
    (net (code "104") (name "unconnected-(J1-NC-Pad6)") (class "Default")
      (node (ref "J1") (pin "6") (pinfunction "NC_6") (pintype "passive+no_connect"))
    )
    (net (code "105") (name "unconnected-(U8-NC-Pad5)") (class "Default")
      (node (ref "U8") (pin "5") (pinfunction "NC_5") (pintype "passive+no_connect"))
    )
    (net (code "106") (name "unconnected-(U9-ID-Pad3)") (class "Default")
      (node (ref "U9") (pin "3") (pinfunction "ID_3") (pintype "passive+no_connect"))
    )
    (net (code "107") (name "unconnected-(U9-NC-Pad5)") (class "Default")
      (node (ref "U9") (pin "5") (pinfunction "NC_5") (pintype "passive+no_connect"))
    )
  )
)
